# VOLTAGE_RESOURCE.net
KiCad netlist of a schematic drawn in Altium Designer
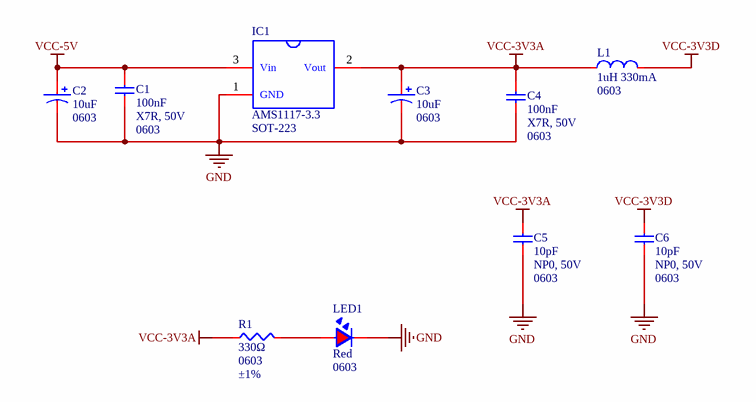
[diagram p0: VOLTAGE_RESOURCE.SchDoc]

(export (version "E")
  (design (tool "Eeschema 10.0.6"))
  (components
    (comp (ref "C1")
      (value "100nF")
      (footprint "C0603")
      (description "50V 100nF X7R ±10% 0603 Multilayer Ceramic Capacitors MLCC - SMD/SMT ROHS")
      (fields
        (field (name "MANUFACTURER") "YAGEO")
        (field (name "MFR. PART") "CC0603KRX7R9BB104")
        (field (name "TEMPERATURE COEFFICIENT") "X7R, 50V")
        (field (name "PACKAGE") "0603")
      )
      (libsource (lib "Capacitor") (part "C0603_MLCC_100nF_X7R_50V"))
    )
    (comp (ref "C2")
      (value "10uF")
      (footprint "C0603 - TANTA")
      (description "10uF ±20% 6.3V Tantalum Capacitors 10Ω@100kHz 0603")
      (fields
        (field (name "MANUFACTURER") "VISHAY")
        (field (name "MFR. PART") "TMCJ0J106MTRF")
        (field (name "PACKAGE") "0603")
      )
      (libsource (lib "Capacitor") (part "C0603_TANTA_10uF_6.3V"))
    )
    (comp (ref "C3")
      (value "10uF")
      (footprint "C0603 - TANTA")
      (description "10uF ±20% 6.3V Tantalum Capacitors 10Ω@100kHz 0603")
      (fields
        (field (name "MANUFACTURER") "VISHAY")
        (field (name "MFR. PART") "TMCJ0J106MTRF")
        (field (name "PACKAGE") "0603")
      )
      (libsource (lib "Capacitor") (part "C0603_TANTA_10uF_6.3V"))
    )
    (comp (ref "C4")
      (value "100nF")
      (footprint "C0603")
      (description "50V 100nF X7R ±10% 0603 Multilayer Ceramic Capacitors MLCC - SMD/SMT ROHS")
      (fields
        (field (name "MANUFACTURER") "YAGEO")
        (field (name "MFR. PART") "CC0603KRX7R9BB104")
        (field (name "TEMPERATURE COEFFICIENT") "X7R, 50V")
        (field (name "PACKAGE") "0603")
      )
      (libsource (lib "Capacitor") (part "C0603_MLCC_100nF_X7R_50V"))
    )
    (comp (ref "C5")
      (value "10pF")
      (footprint "C0603")
      (description "50V 10pF NP0 ±5% 0603 Multilayer Ceramic Capacitors MLCC - SMD/SMT ROHS")
      (fields
        (field (name "MANUFACTURER") "YAGEO")
        (field (name "MFR. PART") "CC0603JRNPO9BN100")
        (field (name "TEMPERATURE COEFFICIENT") "NP0, 50V")
        (field (name "PACKAGE") "0603")
      )
      (libsource (lib "Capacitor") (part "C0603_MLCC_10pF_NP0_50V"))
    )
    (comp (ref "C6")
      (value "10pF")
      (footprint "C0603")
      (description "50V 10pF NP0 ±5% 0603 Multilayer Ceramic Capacitors MLCC - SMD/SMT ROHS")
      (fields
        (field (name "MANUFACTURER") "YAGEO")
        (field (name "MFR. PART") "CC0603JRNPO9BN100")
        (field (name "TEMPERATURE COEFFICIENT") "NP0, 50V")
        (field (name "PACKAGE") "0603")
      )
      (libsource (lib "Capacitor") (part "C0603_MLCC_10pF_NP0_50V"))
    )
    (comp (ref "IC1")
      (value "AMS1117-3.3")
      (footprint "SOT-223")
      (fields
        (field (name "MANUFACTURER") "Advanced Monolithic Systems")
        (field (name "LCSC PART") "C6186")
        (field (name "PACKAGE") "SOT-223")
      )
      (libsource (lib "IC") (part "AMS1117-3.3_SOT-223"))
    )
    (comp (ref "L1")
      (value "1uH 330mA")
      (footprint "L_0603")
      (description "330mA 1uH ±10% 810mΩ Wire-wound chip inductor 0603 Fixed Inductors RoHS")
      (fields
        (field (name "MANUFACTURER") "APV")
        (field (name "MANUFACTURE PART NUMBER") "AHW1608F-1R0KTF")
        (field (name "PACKAGE") "0603")
      )
      (libsource (lib "INDUCTOR") (part "L_1uH_0603_330mA"))
    )
    (comp (ref "LED1")
      (value "Red")
      (footprint "LED0603_RED")
      (description "20mA 230mcd Water Clear -40℃~+85℃ 630nm Red 120° 75mW 1.95V 0603 LED Indication - Discrete ROHS")
      (fields
        (field (name "MANUFACTURER") "Kingbright")
        (field (name "MFR. PART") "APT1608SURCK")
        (field (name "PACKAGE") "0603")
      )
      (libsource (lib "LED") (part "LED0603_Red"))
    )
    (comp (ref "R1")
      (value "330Ω")
      (footprint "R0603")
      (description "100mW Thick Film Resistor 75V ±100ppm/℃ ±1% 330Ω 0603 Chip Resistor - Surface Mount ROHS")
      (fields
        (field (name "MANUFACTURER") "YAGEO")
        (field (name "MFR. PART") "RC0603FR-07330RL")
        (field (name "PACKAGE") "0603")
        (field (name "TOLERANCE") "±1%")
      )
      (libsource (lib "Resistor") (part "R0603_330Ω_±1%"))
    )
  )
  (nets
    (net (code "1") (name "GND") (class "Default")
      (node (ref "C1") (pin "1") (pinfunction "1_1") (pintype "passive"))
      (node (ref "C2") (pin "2") (pinfunction "2_2") (pintype "passive"))
      (node (ref "C3") (pin "2") (pinfunction "2_2") (pintype "passive"))
      (node (ref "C4") (pin "1") (pinfunction "1_1") (pintype "passive"))
      (node (ref "C5") (pin "1") (pinfunction "1_1") (pintype "passive"))
      (node (ref "C6") (pin "1") (pinfunction "1_1") (pintype "passive"))
      (node (ref "IC1") (pin "1") (pinfunction "GND_1") (pintype "passive"))
      (node (ref "LED1") (pin "2") (pinfunction "2_2") (pintype "passive"))
    )
    (net (code "2") (name "Net-(LED1-Pad1)") (class "Default")
      (node (ref "LED1") (pin "1") (pinfunction "1_1") (pintype "passive"))
      (node (ref "R1") (pin "2") (pinfunction "2_2") (pintype "passive"))
    )
    (net (code "3") (name "VCC-3V3A") (class "Default")
      (node (ref "C3") (pin "1") (pinfunction "1_1") (pintype "passive"))
      (node (ref "C4") (pin "2") (pinfunction "2_2") (pintype "passive"))
      (node (ref "C5") (pin "2") (pinfunction "2_2") (pintype "passive"))
      (node (ref "IC1") (pin "2") (pinfunction "Vout_2") (pintype "passive"))
      (node (ref "L1") (pin "1") (pinfunction "1_1") (pintype "passive"))
      (node (ref "R1") (pin "1") (pinfunction "1_1") (pintype "passive"))
    )
    (net (code "4") (name "VCC-3V3D") (class "Default")
      (node (ref "C6") (pin "2") (pinfunction "2_2") (pintype "passive"))
      (node (ref "L1") (pin "2") (pinfunction "2_2") (pintype "passive"))
    )
    (net (code "5") (name "VCC-5V") (class "Default")
      (node (ref "C1") (pin "2") (pinfunction "2_2") (pintype "passive"))
      (node (ref "C2") (pin "1") (pinfunction "1_1") (pintype "passive"))
      (node (ref "IC1") (pin "3") (pinfunction "Vin_3") (pintype "passive"))
    )
  )
)
